# amp_project.net
KiCad netlist of a schematic drawn in EAGLE
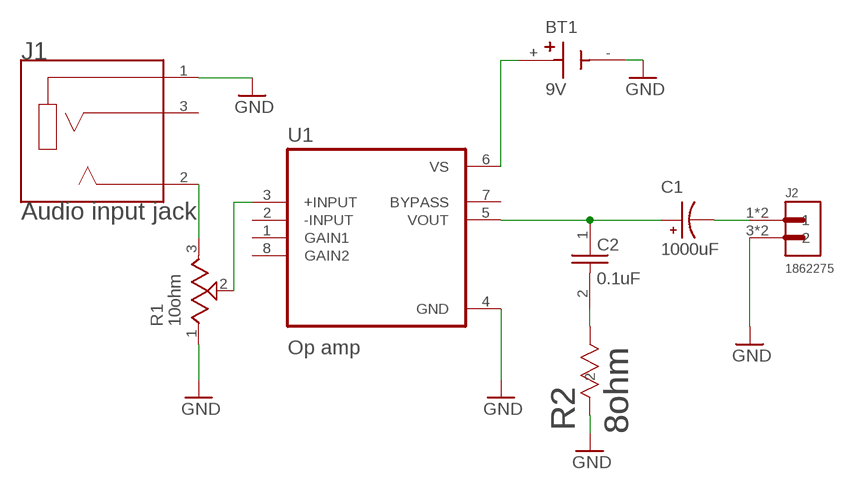
[diagram p0: schematic, sheet 1]

(export (version "E")
  (design (tool "Eeschema 10.0.6"))
  (components
    (comp (ref "BT1")
      (value "9V")
      (footprint "eagle-import:BAT_BH9VPC")
      (fields
        (field (name "DIGI-KEY_PART_NUMBER") "BH9V-PC-ND")
        (field (name "MF") "MPD")
        (field (name "MP") "BH9VPC")
      )
      (libsource (lib "eagle-import") (part "BH9VPC"))
    )
    (comp (ref "C1")
      (value "1000uF")
      (footprint "eagle-import:CAPPRD500W60D1250H1700")
      (fields
        (field (name "DIGI-KEY_PART_NUMBER") "493-12061-1-ND")
        (field (name "MF") "Nichicon")
        (field (name "MP") "UPM1A102MHD6TO")
      )
      (libsource (lib "eagle-import") (part "UPM1A102MHD6TO"))
    )
    (comp (ref "C2")
      (value "0.1uF")
      (footprint "eagle-import:CAPRR254W51L508T318H635P")
      (fields
        (field (name "DIGI-KEY_PART_NUMBER") "BC5209-ND")
        (field (name "MF") "Vishay BC")
        (field (name "MP") "1C10X7R104K050B")
      )
      (libsource (lib "eagle-import") (part "1C10X7R104K050B"))
    )
    (comp (ref "J1")
      (value "Audio input jack")
      (footprint "eagle-import:CUI_SJ2-35853A-SMT-TR")
      (fields (field (name "MF") "CUI Devices") (field (name "MP") "SJ2-35853A-SMT-TR"))
      (libsource (lib "eagle-import") (part "SJ2-35853A-SMT-TR"))
    )
    (comp (ref "J2")
      (value "1862275")
      (footprint "eagle-import:PHOENIX_1862275")
      (fields (field (name "DIGI-KEY_PART_NUMBER") "277-12139-ND") (field (name "MF") "Phoenix Contact"))
      (libsource (lib "eagle-import") (part "1862275"))
    )
    (comp (ref "R1")
      (value "10ohm")
      (footprint "eagle-import:TRIM_3352T-1-103LF")
      (fields
        (field (name "DIGI-KEY_PART_NUMBER") "3352T-103LF-ND")
        (field (name "MF") "Bourns")
        (field (name "MP") "3352T-1-103LF")
      )
      (libsource (lib "eagle-import") (part "3352T-1-103LF"))
    )
    (comp (ref "R2")
      (value "8ohm")
      (footprint "eagle-import:RES_MRS25_VIS")
      (fields (field (name "MANUFACTURER_PART_NUMBER") "MRS25000C1009FCT00"))
      (libsource (lib "eagle-import") (part "MRS25000C1009FCT00"))
    )
    (comp (ref "U1")
      (value "Op amp")
      (footprint "eagle-import:DIP794W45P254L959H508Q8")
      (fields
        (field (name "DIGI-KEY_PART_NUMBER") "296-43960-5-ND")
        (field (name "MF") "Texas Instruments")
        (field (name "MP") "LM386N-4/NOPB")
      )
      (libsource (lib "eagle-import") (part "LM386N-4/NOPB"))
    )
  )
  (nets
    (net (code "1") (name "GND") (class "Default")
      (node (ref "BT1") (pin "-") (pinfunction "-_-") (pintype "passive"))
      (node (ref "J1") (pin "1") (pinfunction "SLEEVE_1") (pintype "passive"))
      (node (ref "J2") (pin "3") (pinfunction "2_3") (pintype "passive"))
      (node (ref "J2") (pin "4") (pinfunction "2_4") (pintype "passive"))
      (node (ref "R1") (pin "1") (pinfunction "CCW_1") (pintype "passive"))
      (node (ref "R2") (pin "2") (pinfunction "2_2") (pintype "passive"))
      (node (ref "U1") (pin "4") (pinfunction "GND_4") (pintype "power_in"))
    )
    (net (code "2") (name "Net-(C1-PadN)") (class "Default")
      (node (ref "C1") (pin "N") (pinfunction "N_N") (pintype "passive"))
      (node (ref "J2") (pin "1") (pinfunction "1_1") (pintype "passive"))
      (node (ref "J2") (pin "2") (pinfunction "1_2") (pintype "passive"))
    )
    (net (code "3") (name "Net-(C2-Pad2)") (class "Default")
      (node (ref "C2") (pin "2") (pinfunction "2_2") (pintype "passive"))
      (node (ref "R2") (pin "1") (pinfunction "1_1") (pintype "passive"))
    )
    (net (code "4") (name "Net-(J1-TIP)") (class "Default")
      (node (ref "J1") (pin "2") (pinfunction "TIP_2") (pintype "passive"))
      (node (ref "R1") (pin "3") (pinfunction "CW_3") (pintype "passive"))
    )
    (net (code "5") (name "Net-(R1-WIPER)") (class "Default")
      (node (ref "R1") (pin "2") (pinfunction "WIPER_2") (pintype "passive"))
      (node (ref "U1") (pin "3") (pinfunction "+INPUT_3") (pintype "input"))
    )
    (net (code "6") (name "Net-(U1-VOUT)") (class "Default")
      (node (ref "C1") (pin "P") (pinfunction "P_P") (pintype "passive"))
      (node (ref "C2") (pin "1") (pinfunction "1_1") (pintype "passive"))
      (node (ref "U1") (pin "5") (pinfunction "VOUT_5") (pintype "output"))
    )
    (net (code "7") (name "Net-(U1-VS)") (class "Default")
      (node (ref "BT1") (pin "+") (pinfunction "+_+") (pintype "passive"))
      (node (ref "U1") (pin "6") (pinfunction "VS_6") (pintype "power_in"))
    )
    (net (code "8") (name "unconnected-(J1-RING-Pad3)") (class "Default")
      (node (ref "J1") (pin "3") (pinfunction "RING_3") (pintype "passive"))
    )
    (net (code "9") (name "unconnected-(U1--INPUT-Pad2)") (class "Default")
      (node (ref "U1") (pin "2") (pinfunction "-INPUT_2") (pintype "input"))
    )
    (net (code "10") (name "unconnected-(U1-BYPASS-Pad7)") (class "Default")
      (node (ref "U1") (pin "7") (pinfunction "BYPASS_7") (pintype "output"))
    )
    (net (code "11") (name "unconnected-(U1-GAIN1-Pad1)") (class "Default")
      (node (ref "U1") (pin "1") (pinfunction "GAIN1_1") (pintype "input"))
    )
    (net (code "12") (name "unconnected-(U1-GAIN2-Pad8)") (class "Default")
      (node (ref "U1") (pin "8") (pinfunction "GAIN2_8") (pintype "input"))
    )
  )
)
